# BSP.net
KiCad netlist of a schematic drawn in Altium Designer
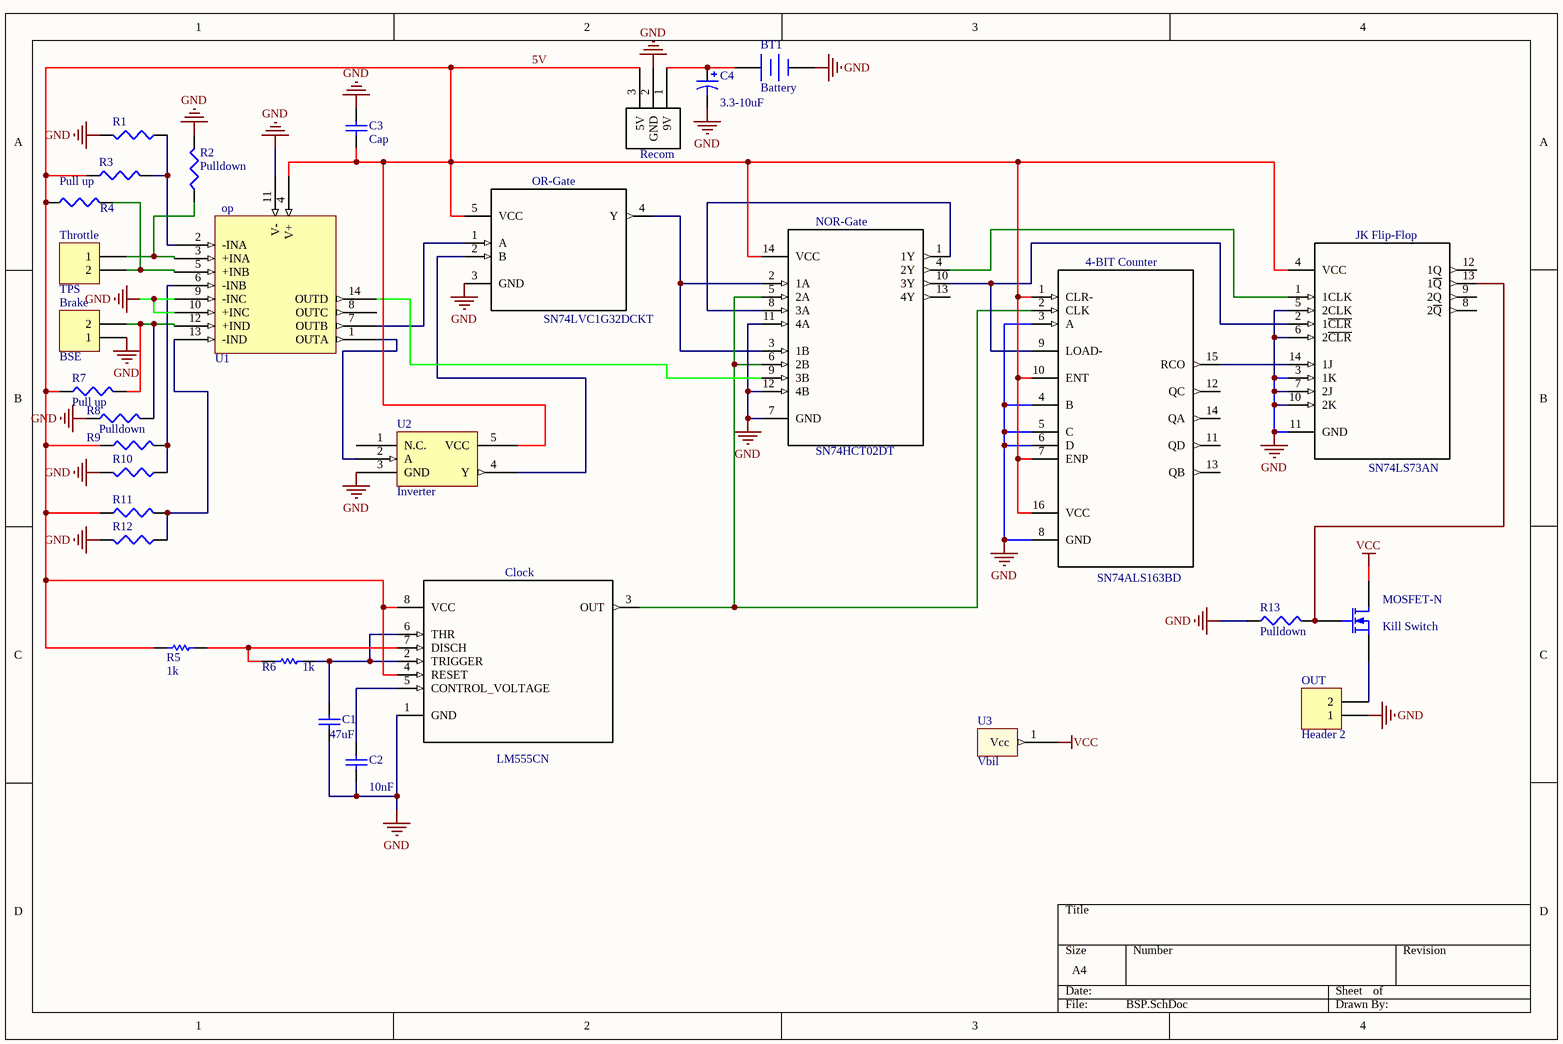
[diagram p0: BSP.SchDoc]

(export (version "E")
  (design (tool "Eeschema 10.0.6"))
  (components
    (comp (ref "*") (value "Recom") (footprint "RECOMM") (libsource (lib "recom") (part "Component_1")))
    (comp (ref "4-BIT Counter")
      (value "SN74ALS163BD")
      (footprint "SOIC127P600X175-16N")
      (description "Counter Single 4-Bit Sync Binary UP 16-Pin SOIC Tube")
      (fields (field (name "MF") "Texas Instruments"))
      (libsource (lib "SN74ALS163BD") (part "SN74ALS163BD"))
    )
    (comp (ref "Brake")
      (value "BSE")
      (footprint "HDR1X2")
      (description "Header, 2-Pin")
      (fields (field (name "PUBLISHER") "Altium Limited"))
      (libsource (lib "Miscellaneous Connectors") (part "Header 2"))
    )
    (comp (ref "BT1")
      (value "Battery")
      (footprint "HDR1X2")
      (description "Multicell Battery")
      (fields (field (name "PUBLISHER") "Altium Limited"))
      (libsource (lib "Miscellaneous Devices") (part "Battery"))
    )
    (comp (ref "C1")
      (value "47uF")
      (footprint "C5750")
      (description "Capacitor")
      (fields (field (name "PUBLISHER") "Altium Limited"))
      (libsource (lib "Miscellaneous Devices") (part "Cap"))
    )
    (comp (ref "C2")
      (value "10nF")
      (footprint "Resistor0805")
      (description "Capacitor")
      (fields (field (name "PUBLISHER") "Altium Limited"))
      (libsource (lib "Miscellaneous Devices") (part "Cap"))
    )
    (comp (ref "C3")
      (value "Cap")
      (footprint "Resistor0805")
      (description "Capacitor")
      (fields (field (name "PUBLISHER") "Altium Limited"))
      (libsource (lib "Miscellaneous Devices") (part "Cap"))
    )
    (comp (ref "C4")
      (value "3.3-10uF")
      (footprint "CAPR5-4X5")
      (description "Polarized Capacitor (Radial)")
      (fields (field (name "Comment") "Cap Pol1") (field (name "PUBLISHER") "Altium Limited"))
      (libsource (lib "Miscellaneous Devices") (part "Cap Pol1"))
    )
    (comp (ref "Clock")
      (value "LM555CN")
      (footprint "DIP254P762X533-8")
      (description "Highly stable 555 timer for generating accurate time delays and oscillation 8-PDIP 0 to 70")
      (fields (field (name "MP") "LM555CN/NOPB") (field (name "MF") "Texas Instruments"))
      (libsource (lib "LM555CN") (part "LM555CN"))
    )
    (comp (ref "JK Flip-Flop")
      (value "SN74LS73AN")
      (footprint "DIP254P762X508-14")
      (description "Flip Flop JK-Master-Slave Type Neg-Edge 2-Element 14-Pin PDIP Tube")
      (fields (field (name "MF") "Texas Instruments"))
      (libsource (lib "SN74LS73AN") (part "SN74LS73AN"))
    )
    (comp (ref "MOSFET-N")
      (value "Kill Switch")
      (footprint "DPAK228P998X280-3N")
      (description "N-Channel MOSFET")
      (fields (field (name "PUBLISHER") "Altium Limited"))
      (libsource (lib "Miscellaneous Devices") (part "MOSFET-N"))
    )
    (comp (ref "NOR-Gate")
      (value "SN74HCT02DT")
      (footprint "SOIC127P600X175-14N")
      (description "Quadruple 2-Input Positive-NO Gates 14-SOIC -40 to 85")
      (fields (field (name "MF") "Texas Instruments"))
      (libsource (lib "SN74HCT02DT") (part "SN74HCT02DT"))
    )
    (comp (ref "OR-Gate")
      (value "SN74LVC1G32DCKT")
      (footprint "SOT65P210X110-5N")
      (description "Single 2-Input Positive-O Gate 5-SC70 -40 to 125")
      (fields (field (name "MF") "Texas Instruments"))
      (libsource (lib "SN74LVC1G32DCKT") (part "SN74LVC1G32DCKT"))
    )
    (comp (ref "OUT")
      (value "Header 2")
      (footprint "HDR1X2")
      (description "Header, 2-Pin")
      (fields (field (name "PUBLISHER") "Altium Limited"))
      (libsource (lib "Miscellaneous Connectors") (part "Header 2"))
    )
    (comp (ref "R1")
      (value "~")
      (footprint "Resistor0805")
      (description "Resistor")
      (fields (field (name "PUBLISHER") "Altium Limited"))
      (libsource (lib "Miscellaneous Devices") (part "Res3"))
    )
    (comp (ref "R2")
      (value "Pulldown")
      (footprint "Resistor0805")
      (description "Resistor")
      (fields (field (name "PUBLISHER") "Altium Limited"))
      (libsource (lib "Miscellaneous Devices") (part "Res3"))
    )
    (comp (ref "R3")
      (value "~")
      (footprint "Resistor0805")
      (description "Resistor")
      (fields (field (name "PUBLISHER") "Altium Limited"))
      (libsource (lib "Miscellaneous Devices") (part "Res3"))
    )
    (comp (ref "R4")
      (value "Pull up")
      (footprint "Resistor0805")
      (description "Resistor")
      (fields (field (name "PUBLISHER") "Altium Limited"))
      (libsource (lib "Miscellaneous Devices") (part "Res3"))
    )
    (comp (ref "R5")
      (value "R5")
      (footprint "Resistor0805")
      (description "Resistor")
      (fields (field (name "ALTIUM_VALUE") "1k") (field (name "PUBLISHER") "Altium Limited"))
      (libsource (lib "Miscellaneous Devices") (part "Res1"))
    )
    (comp (ref "R6")
      (value "1k")
      (footprint "Resistor0805")
      (description "Resistor")
      (fields (field (name "PUBLISHER") "Altium Limited"))
      (libsource (lib "Miscellaneous Devices") (part "Res1"))
    )
    (comp (ref "R7")
      (value "Pull up")
      (footprint "Resistor0805")
      (description "Resistor")
      (fields (field (name "PUBLISHER") "Altium Limited"))
      (libsource (lib "Miscellaneous Devices") (part "Res3"))
    )
    (comp (ref "R8")
      (value "Pulldown")
      (footprint "Resistor0805")
      (description "Resistor")
      (fields (field (name "PUBLISHER") "Altium Limited"))
      (libsource (lib "Miscellaneous Devices") (part "Res3"))
    )
    (comp (ref "R9")
      (value "~")
      (footprint "Resistor0805")
      (description "Resistor")
      (fields (field (name "PUBLISHER") "Altium Limited"))
      (libsource (lib "Miscellaneous Devices") (part "Res3"))
    )
    (comp (ref "R10")
      (value "~")
      (footprint "Resistor0805")
      (description "Resistor")
      (fields (field (name "PUBLISHER") "Altium Limited"))
      (libsource (lib "Miscellaneous Devices") (part "Res3"))
    )
    (comp (ref "R11")
      (value "~")
      (footprint "Resistor0805")
      (description "Resistor")
      (fields (field (name "PUBLISHER") "Altium Limited"))
      (libsource (lib "Miscellaneous Devices") (part "Res3"))
    )
    (comp (ref "R12")
      (value "~")
      (footprint "Resistor0805")
      (description "Resistor")
      (fields (field (name "PUBLISHER") "Altium Limited"))
      (libsource (lib "Miscellaneous Devices") (part "Res3"))
    )
    (comp (ref "R13")
      (value "Pulldown")
      (footprint "Resistor0805")
      (description "Resistor")
      (fields (field (name "PUBLISHER") "Altium Limited"))
      (libsource (lib "Miscellaneous Devices") (part "Res3"))
    )
    (comp (ref "Throttle")
      (value "TPS")
      (footprint "HDR1X2H")
      (description "Header, 2-Pin, Right Angle")
      (fields (field (name "PUBLISHER") "Altium Limited"))
      (libsource (lib "Miscellaneous Connectors") (part "Header 2H"))
    )
    (comp (ref "U1")
      (value "op")
      (footprint "SOP127P600X175-14N")
      (description "OPA4196")
      (libsource (lib "SN74LVC1G32DCKT") (part "op"))
    )
    (comp (ref "U2")
      (value "Inverter")
      (footprint "SOT95P245X145-5N")
      (libsource (lib "NOT") (part "Component_1"))
    )
    (comp (ref "U3") (value "Vbil") (footprint "VCC") (libsource (lib "NOT") (part "Vbil")))
  )
  (nets
    (net (code "1") (name "/5V") (class "Default")
      (node (ref "*") (pin "3") (pinfunction "5V_3") (pintype "passive"))
      (node (ref "4-BIT Counter") (pin "1") (pinfunction "CLR-_1") (pintype "input"))
      (node (ref "4-BIT Counter") (pin "10") (pinfunction "ENT_10") (pintype "passive"))
      (node (ref "4-BIT Counter") (pin "16") (pinfunction "VCC_16") (pintype "power_in"))
      (node (ref "4-BIT Counter") (pin "7") (pinfunction "ENP_7") (pintype "passive"))
      (node (ref "C3") (pin "2") (pinfunction "2_2") (pintype "passive"))
      (node (ref "Clock") (pin "4") (pinfunction "RESET_4") (pintype "input"))
      (node (ref "Clock") (pin "8") (pinfunction "VCC_8") (pintype "power_in"))
      (node (ref "JK Flip-Flop") (pin "4") (pinfunction "VCC_4") (pintype "power_in"))
      (node (ref "NOR-Gate") (pin "14") (pinfunction "VCC_14") (pintype "power_in"))
      (node (ref "OR-Gate") (pin "5") (pinfunction "VCC_5") (pintype "power_in"))
      (node (ref "R11") (pin "1") (pinfunction "1_1") (pintype "passive"))
      (node (ref "R3") (pin "1") (pinfunction "1_1") (pintype "passive"))
      (node (ref "R4") (pin "1") (pinfunction "1_1") (pintype "passive"))
      (node (ref "R5") (pin "2") (pinfunction "2_2") (pintype "passive"))
      (node (ref "R7") (pin "1") (pinfunction "1_1") (pintype "passive"))
      (node (ref "R9") (pin "1") (pinfunction "1_1") (pintype "passive"))
      (node (ref "U1") (pin "4") (pinfunction "V+_4") (pintype "input"))
      (node (ref "U2") (pin "5") (pinfunction "VCC_5") (pintype "power_in"))
    )
    (net (code "2") (name "GND") (class "Default")
      (node (ref "*") (pin "2") (pinfunction "GND_2") (pintype "passive"))
      (node (ref "4-BIT Counter") (pin "3") (pinfunction "A_3") (pintype "input"))
      (node (ref "4-BIT Counter") (pin "4") (pinfunction "B_4") (pintype "passive"))
      (node (ref "4-BIT Counter") (pin "5") (pinfunction "C_5") (pintype "passive"))
      (node (ref "4-BIT Counter") (pin "6") (pinfunction "D_6") (pintype "passive"))
      (node (ref "4-BIT Counter") (pin "8") (pinfunction "GND_8") (pintype "power_in"))
      (node (ref "BT1") (pin "2") (pinfunction "-_2") (pintype "passive"))
      (node (ref "Brake") (pin "1") (pinfunction "1_1") (pintype "passive"))
      (node (ref "C1") (pin "1") (pinfunction "1_1") (pintype "passive"))
      (node (ref "C2") (pin "1") (pinfunction "1_1") (pintype "passive"))
      (node (ref "C3") (pin "1") (pinfunction "1_1") (pintype "passive"))
      (node (ref "C4") (pin "2") (pinfunction "2_2") (pintype "passive"))
      (node (ref "Clock") (pin "1") (pinfunction "GND_1") (pintype "passive"))
      (node (ref "JK Flip-Flop") (pin "10") (pinfunction "2K_10") (pintype "input"))
      (node (ref "JK Flip-Flop") (pin "11") (pinfunction "GND_11") (pintype "passive"))
      (node (ref "JK Flip-Flop") (pin "3") (pinfunction "1K_3") (pintype "input"))
      (node (ref "JK Flip-Flop") (pin "5") (pinfunction "2CLK_5") (pintype "input"))
      (node (ref "JK Flip-Flop") (pin "6") (pinfunction "2~{CLR}_6") (pintype "input"))
      (node (ref "JK Flip-Flop") (pin "7") (pinfunction "2J_7") (pintype "input"))
      (node (ref "NOR-Gate") (pin "11") (pinfunction "4A_11") (pintype "input"))
      (node (ref "NOR-Gate") (pin "12") (pinfunction "4B_12") (pintype "input"))
      (node (ref "NOR-Gate") (pin "7") (pinfunction "GND_7") (pintype "passive"))
      (node (ref "OR-Gate") (pin "3") (pinfunction "GND_3") (pintype "passive"))
      (node (ref "OUT") (pin "1") (pinfunction "1_1") (pintype "passive"))
      (node (ref "R1") (pin "2") (pinfunction "2_2") (pintype "passive"))
      (node (ref "R10") (pin "2") (pinfunction "2_2") (pintype "passive"))
      (node (ref "R12") (pin "2") (pinfunction "2_2") (pintype "passive"))
      (node (ref "R13") (pin "1") (pinfunction "1_1") (pintype "passive"))
      (node (ref "R2") (pin "2") (pinfunction "2_2") (pintype "passive"))
      (node (ref "R8") (pin "1") (pinfunction "1_1") (pintype "passive"))
      (node (ref "U1") (pin "10") (pinfunction "+INC_10") (pintype "input"))
      (node (ref "U1") (pin "11") (pinfunction "V-_11") (pintype "input"))
      (node (ref "U1") (pin "9") (pinfunction "-INC_9") (pintype "input"))
      (node (ref "U2") (pin "3") (pinfunction "GND_3") (pintype "power_in"))
    )
    (net (code "3") (name "Net-(*-9V)") (class "Default")
      (node (ref "*") (pin "1") (pinfunction "9V_1") (pintype "passive"))
      (node (ref "BT1") (pin "1") (pinfunction "+_1") (pintype "passive"))
      (node (ref "C4") (pin "1") (pinfunction "1_1") (pintype "passive"))
    )
    (net (code "4") (name "Net-(4-BIT Counter-CLK)") (class "Default")
      (node (ref "4-BIT Counter") (pin "2") (pinfunction "CLK_2") (pintype "input"))
      (node (ref "Clock") (pin "3") (pinfunction "OUT_3") (pintype "output"))
      (node (ref "NOR-Gate") (pin "5") (pinfunction "2A_5") (pintype "input"))
      (node (ref "NOR-Gate") (pin "6") (pinfunction "2B_6") (pintype "input"))
    )
    (net (code "5") (name "Net-(4-BIT Counter-LOAD-)") (class "Default")
      (node (ref "4-BIT Counter") (pin "9") (pinfunction "LOAD-_9") (pintype "passive"))
      (node (ref "JK Flip-Flop") (pin "2") (pinfunction "1~{CLR}_2") (pintype "input"))
      (node (ref "NOR-Gate") (pin "10") (pinfunction "3Y_10") (pintype "output"))
    )
    (net (code "6") (name "Net-(4-BIT Counter-RCO)") (class "Default")
      (node (ref "4-BIT Counter") (pin "15") (pinfunction "RCO_15") (pintype "output"))
      (node (ref "JK Flip-Flop") (pin "14") (pinfunction "1J_14") (pintype "input"))
    )
    (net (code "7") (name "Net-(Clock-CONTROL_VOLTAGE)") (class "Default")
      (node (ref "C2") (pin "2") (pinfunction "2_2") (pintype "passive"))
      (node (ref "Clock") (pin "5") (pinfunction "CONTROL_VOLTAGE_5") (pintype "input"))
    )
    (net (code "8") (name "Net-(Clock-DISCH)") (class "Default")
      (node (ref "Clock") (pin "7") (pinfunction "DISCH_7") (pintype "input"))
      (node (ref "R5") (pin "1") (pinfunction "1_1") (pintype "passive"))
      (node (ref "R6") (pin "2") (pinfunction "2_2") (pintype "passive"))
    )
    (net (code "9") (name "Net-(Clock-THR)") (class "Default")
      (node (ref "C1") (pin "2") (pinfunction "2_2") (pintype "passive"))
      (node (ref "Clock") (pin "2") (pinfunction "TRIGGER_2") (pintype "input"))
      (node (ref "Clock") (pin "6") (pinfunction "THR_6") (pintype "input"))
      (node (ref "R6") (pin "1") (pinfunction "1_1") (pintype "passive"))
    )
    (net (code "10") (name "Net-(JK Flip-Flop-1CLK)") (class "Default")
      (node (ref "JK Flip-Flop") (pin "1") (pinfunction "1CLK_1") (pintype "input"))
      (node (ref "NOR-Gate") (pin "4") (pinfunction "2Y_4") (pintype "output"))
    )
    (net (code "11") (name "Net-(JK Flip-Flop-1~{Q})") (class "Default")
      (node (ref "JK Flip-Flop") (pin "13") (pinfunction "1~{Q}_13") (pintype "output"))
      (node (ref "MOSFET-N") (pin "2") (pinfunction "G_2") (pintype "passive"))
      (node (ref "R13") (pin "2") (pinfunction "2_2") (pintype "passive"))
    )
    (net (code "12") (name "Net-(MOSFET-N-S)") (class "Default")
      (node (ref "MOSFET-N") (pin "3") (pinfunction "S_3") (pintype "passive"))
      (node (ref "OUT") (pin "2") (pinfunction "2_2") (pintype "passive"))
    )
    (net (code "13") (name "Net-(NOR-Gate-1A)") (class "Default")
      (node (ref "NOR-Gate") (pin "2") (pinfunction "1A_2") (pintype "input"))
      (node (ref "NOR-Gate") (pin "3") (pinfunction "1B_3") (pintype "input"))
      (node (ref "OR-Gate") (pin "4") (pinfunction "Y_4") (pintype "output"))
    )
    (net (code "14") (name "Net-(NOR-Gate-1Y)") (class "Default")
      (node (ref "NOR-Gate") (pin "1") (pinfunction "1Y_1") (pintype "output"))
      (node (ref "NOR-Gate") (pin "8") (pinfunction "3A_8") (pintype "input"))
    )
    (net (code "15") (name "Net-(NOR-Gate-3B)") (class "Default")
      (node (ref "NOR-Gate") (pin "9") (pinfunction "3B_9") (pintype "input"))
      (node (ref "U1") (pin "14") (pinfunction "OUTD_14") (pintype "output"))
    )
    (net (code "16") (name "Net-(OR-Gate-A)") (class "Default")
      (node (ref "OR-Gate") (pin "1") (pinfunction "A_1") (pintype "input"))
      (node (ref "U1") (pin "7") (pinfunction "OUTB_7") (pintype "output"))
    )
    (net (code "17") (name "Net-(OR-Gate-B)") (class "Default")
      (node (ref "OR-Gate") (pin "2") (pinfunction "B_2") (pintype "input"))
      (node (ref "U2") (pin "4") (pinfunction "Y_4") (pintype "output"))
    )
    (net (code "18") (name "Net-(Throttle-1)") (class "Default")
      (node (ref "R2") (pin "1") (pinfunction "1_1") (pintype "passive"))
      (node (ref "Throttle") (pin "2") (pinfunction "1_2") (pintype "passive"))
      (node (ref "U1") (pin "3") (pinfunction "+INA_3") (pintype "input"))
    )
    (net (code "19") (name "Net-(Throttle-2)") (class "Default")
      (node (ref "R4") (pin "2") (pinfunction "2_2") (pintype "passive"))
      (node (ref "Throttle") (pin "1") (pinfunction "2_1") (pintype "passive"))
      (node (ref "U1") (pin "5") (pinfunction "+INB_5") (pintype "input"))
    )
    (net (code "20") (name "Net-(U1-+IND)") (class "Default")
      (node (ref "Brake") (pin "2") (pinfunction "2_2") (pintype "passive"))
      (node (ref "R7") (pin "2") (pinfunction "2_2") (pintype "passive"))
      (node (ref "R8") (pin "2") (pinfunction "2_2") (pintype "passive"))
      (node (ref "U1") (pin "12") (pinfunction "+IND_12") (pintype "input"))
    )
    (net (code "21") (name "Net-(U1--INA)") (class "Default")
      (node (ref "R1") (pin "1") (pinfunction "1_1") (pintype "passive"))
      (node (ref "R3") (pin "2") (pinfunction "2_2") (pintype "passive"))
      (node (ref "U1") (pin "2") (pinfunction "-INA_2") (pintype "input"))
    )
    (net (code "22") (name "Net-(U1--INB)") (class "Default")
      (node (ref "R10") (pin "1") (pinfunction "1_1") (pintype "passive"))
      (node (ref "R9") (pin "2") (pinfunction "2_2") (pintype "passive"))
      (node (ref "U1") (pin "6") (pinfunction "-INB_6") (pintype "input"))
    )
    (net (code "23") (name "Net-(U1--IND)") (class "Default")
      (node (ref "R11") (pin "2") (pinfunction "2_2") (pintype "passive"))
      (node (ref "R12") (pin "1") (pinfunction "1_1") (pintype "passive"))
      (node (ref "U1") (pin "13") (pinfunction "-IND_13") (pintype "input"))
    )
    (net (code "24") (name "Net-(U1-OUTA)") (class "Default")
      (node (ref "U1") (pin "1") (pinfunction "OUTA_1") (pintype "output"))
      (node (ref "U2") (pin "2") (pinfunction "A_2") (pintype "input"))
    )
    (net (code "25") (name "VCC") (class "Default")
      (node (ref "MOSFET-N") (pin "1") (pinfunction "D_1") (pintype "passive"))
      (node (ref "U3") (pin "1") (pinfunction "Vcc_1") (pintype "output"))
    )
    (net (code "26") (name "unconnected-(4-BIT Counter-QA-Pad14)") (class "Default")
      (node (ref "4-BIT Counter") (pin "14") (pinfunction "QA_14") (pintype "output"))
    )
    (net (code "27") (name "unconnected-(4-BIT Counter-QB-Pad13)") (class "Default")
      (node (ref "4-BIT Counter") (pin "13") (pinfunction "QB_13") (pintype "output"))
    )
    (net (code "28") (name "unconnected-(4-BIT Counter-QC-Pad12)") (class "Default")
      (node (ref "4-BIT Counter") (pin "12") (pinfunction "QC_12") (pintype "output"))
    )
    (net (code "29") (name "unconnected-(4-BIT Counter-QD-Pad11)") (class "Default")
      (node (ref "4-BIT Counter") (pin "11") (pinfunction "QD_11") (pintype "output"))
    )
    (net (code "30") (name "unconnected-(JK Flip-Flop-1Q-Pad12)") (class "Default")
      (node (ref "JK Flip-Flop") (pin "12") (pinfunction "1Q_12") (pintype "output"))
    )
    (net (code "31") (name "unconnected-(JK Flip-Flop-2Q-Pad9)") (class "Default")
      (node (ref "JK Flip-Flop") (pin "9") (pinfunction "2Q_9") (pintype "output"))
    )
    (net (code "32") (name "unconnected-(JK Flip-Flop-2~{Q}-Pad8)") (class "Default")
      (node (ref "JK Flip-Flop") (pin "8") (pinfunction "2~{Q}_8") (pintype "output"))
    )
    (net (code "33") (name "unconnected-(NOR-Gate-4Y-Pad13)") (class "Default")
      (node (ref "NOR-Gate") (pin "13") (pinfunction "4Y_13") (pintype "output"))
    )
    (net (code "34") (name "unconnected-(U1-OUTC-Pad8)") (class "Default")
      (node (ref "U1") (pin "8") (pinfunction "OUTC_8") (pintype "output"))
    )
    (net (code "35") (name "unconnected-(U2-N.C.-Pad1)") (class "Default")
      (node (ref "U2") (pin "1") (pinfunction "N.C._1") (pintype "passive"))
    )
  )
)
